# Baby_TX_Mod.net
KiCad netlist of a schematic drawn in EAGLE
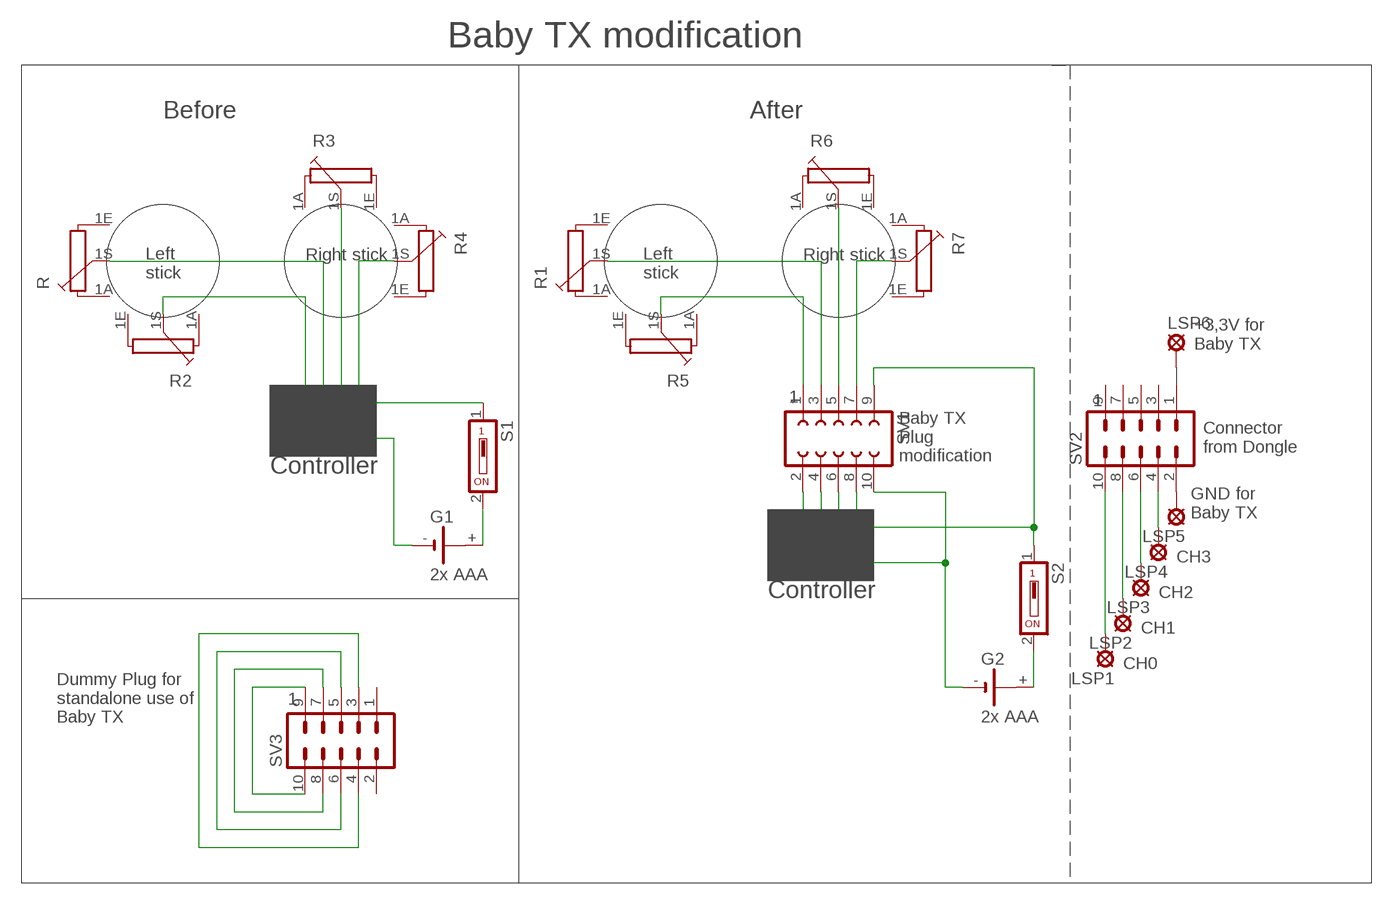
[diagram p0: schematic, sheet 1]

(export (version "E")
  (design (tool "Eeschema 10.0.6"))
  (components
    (comp (ref "G1")
      (value "2x AAA")
      (footprint "eagle-import:CR2032H")
      (libsource (lib "eagle-import") (part "CR2032H"))
    )
    (comp (ref "G2")
      (value "2x AAA")
      (footprint "eagle-import:CR2032H")
      (libsource (lib "eagle-import") (part "CR2032H"))
    )
    (comp (ref "LSP1")
      (value "LSP10")
      (footprint "eagle-import:LSP10")
      (libsource (lib "eagle-import") (part "LSP10"))
    )
    (comp (ref "LSP2")
      (value "LSP10")
      (footprint "eagle-import:LSP10")
      (libsource (lib "eagle-import") (part "LSP10"))
    )
    (comp (ref "LSP3")
      (value "LSP10")
      (footprint "eagle-import:LSP10")
      (libsource (lib "eagle-import") (part "LSP10"))
    )
    (comp (ref "LSP4")
      (value "LSP10")
      (footprint "eagle-import:LSP10")
      (libsource (lib "eagle-import") (part "LSP10"))
    )
    (comp (ref "LSP5")
      (value "LSP10")
      (footprint "eagle-import:LSP10")
      (libsource (lib "eagle-import") (part "LSP10"))
    )
    (comp (ref "LSP6")
      (value "LSP10")
      (footprint "eagle-import:LSP10")
      (libsource (lib "eagle-import") (part "LSP10"))
    )
    (comp (ref "R")
      (value "PC16S")
      (footprint "eagle-import:PC16S")
      (libsource (lib "eagle-import") (part "PC16S"))
    )
    (comp (ref "R1")
      (value "PC16S")
      (footprint "eagle-import:PC16S")
      (libsource (lib "eagle-import") (part "PC16S"))
    )
    (comp (ref "R2")
      (value "PC16S")
      (footprint "eagle-import:PC16S")
      (libsource (lib "eagle-import") (part "PC16S"))
    )
    (comp (ref "R3")
      (value "PC16S")
      (footprint "eagle-import:PC16S")
      (libsource (lib "eagle-import") (part "PC16S"))
    )
    (comp (ref "R4")
      (value "PC16S")
      (footprint "eagle-import:PC16S")
      (libsource (lib "eagle-import") (part "PC16S"))
    )
    (comp (ref "R5")
      (value "PC16S")
      (footprint "eagle-import:PC16S")
      (libsource (lib "eagle-import") (part "PC16S"))
    )
    (comp (ref "R6")
      (value "PC16S")
      (footprint "eagle-import:PC16S")
      (libsource (lib "eagle-import") (part "PC16S"))
    )
    (comp (ref "R7")
      (value "PC16S")
      (footprint "eagle-import:PC16S")
      (libsource (lib "eagle-import") (part "PC16S"))
    )
    (comp (ref "S1")
      (value "SD4-01")
      (footprint "eagle-import:SD4-01")
      (libsource (lib "eagle-import") (part "SD4-01"))
    )
    (comp (ref "S2")
      (value "SD4-01")
      (footprint "eagle-import:SD4-01")
      (libsource (lib "eagle-import") (part "SD4-01"))
    )
    (comp (ref "SV1")
      (value "FE05-2")
      (footprint "eagle-import:FE05-2")
      (libsource (lib "eagle-import") (part "FE05-2"))
    )
    (comp (ref "SV2")
      (value "MA05-2")
      (footprint "eagle-import:MA05-2")
      (libsource (lib "eagle-import") (part "MA05-2"))
    )
    (comp (ref "SV3")
      (value "MA05-2")
      (footprint "eagle-import:MA05-2")
      (libsource (lib "eagle-import") (part "MA05-2"))
    )
  )
  (nets
    (net (code "1") (name "Net-(G1-Pad+)") (class "Default")
      (node (ref "G1") (pin "+") (pinfunction "+_+") (pintype "passive"))
      (node (ref "S1") (pin "2") (pinfunction "2_2") (pintype "passive"))
    )
    (net (code "2") (name "Net-(G2-Pad+)") (class "Default")
      (node (ref "G2") (pin "+") (pinfunction "+_+") (pintype "passive"))
      (node (ref "S2") (pin "2") (pinfunction "2_2") (pintype "passive"))
    )
    (net (code "3") (name "Net-(G2-Pad-)") (class "Default")
      (node (ref "G2") (pin "-") (pinfunction "-_-") (pintype "passive"))
      (node (ref "SV1") (pin "10") (pinfunction "10_10") (pintype "passive"))
    )
    (net (code "4") (name "Net-(LSP1-PadMP)") (class "Default")
      (node (ref "LSP1") (pin "MP") (pinfunction "MP_MP") (pintype "passive"))
      (node (ref "SV2") (pin "10") (pinfunction "10_10") (pintype "passive"))
    )
    (net (code "5") (name "Net-(LSP2-PadMP)") (class "Default")
      (node (ref "LSP2") (pin "MP") (pinfunction "MP_MP") (pintype "passive"))
      (node (ref "SV2") (pin "8") (pinfunction "8_8") (pintype "passive"))
    )
    (net (code "6") (name "Net-(LSP3-PadMP)") (class "Default")
      (node (ref "LSP3") (pin "MP") (pinfunction "MP_MP") (pintype "passive"))
      (node (ref "SV2") (pin "6") (pinfunction "6_6") (pintype "passive"))
    )
    (net (code "7") (name "Net-(LSP4-PadMP)") (class "Default")
      (node (ref "LSP4") (pin "MP") (pinfunction "MP_MP") (pintype "passive"))
      (node (ref "SV2") (pin "4") (pinfunction "4_4") (pintype "passive"))
    )
    (net (code "8") (name "Net-(LSP5-PadMP)") (class "Default")
      (node (ref "LSP5") (pin "MP") (pinfunction "MP_MP") (pintype "passive"))
      (node (ref "SV2") (pin "2") (pinfunction "2_2") (pintype "passive"))
    )
    (net (code "9") (name "Net-(R1-Pad1S)") (class "Default")
      (node (ref "R1") (pin "1S") (pinfunction "1S_1S") (pintype "passive"))
      (node (ref "SV1") (pin "3") (pinfunction "3_3") (pintype "passive"))
    )
    (net (code "10") (name "Net-(R5-Pad1S)") (class "Default")
      (node (ref "R5") (pin "1S") (pinfunction "1S_1S") (pintype "passive"))
      (node (ref "SV1") (pin "1") (pinfunction "1_1") (pintype "passive"))
    )
    (net (code "11") (name "Net-(R6-Pad1S)") (class "Default")
      (node (ref "R6") (pin "1S") (pinfunction "1S_1S") (pintype "passive"))
      (node (ref "SV1") (pin "5") (pinfunction "5_5") (pintype "passive"))
    )
    (net (code "12") (name "Net-(R7-Pad1S)") (class "Default")
      (node (ref "R7") (pin "1S") (pinfunction "1S_1S") (pintype "passive"))
      (node (ref "SV1") (pin "7") (pinfunction "7_7") (pintype "passive"))
    )
    (net (code "13") (name "Net-(S2-Pad1)") (class "Default")
      (node (ref "S2") (pin "1") (pinfunction "1_1") (pintype "passive"))
      (node (ref "SV1") (pin "9") (pinfunction "9_9") (pintype "passive"))
    )
    (net (code "14") (name "Net-(SV3-Pad3)") (class "Default")
      (node (ref "SV3") (pin "3") (pinfunction "3_3") (pintype "passive"))
      (node (ref "SV3") (pin "4") (pinfunction "4_4") (pintype "passive"))
    )
    (net (code "15") (name "Net-(SV3-Pad5)") (class "Default")
      (node (ref "SV3") (pin "5") (pinfunction "5_5") (pintype "passive"))
      (node (ref "SV3") (pin "6") (pinfunction "6_6") (pintype "passive"))
    )
    (net (code "16") (name "Net-(SV3-Pad7)") (class "Default")
      (node (ref "SV3") (pin "7") (pinfunction "7_7") (pintype "passive"))
      (node (ref "SV3") (pin "8") (pinfunction "8_8") (pintype "passive"))
    )
    (net (code "17") (name "Net-(SV3-Pad10)") (class "Default")
      (node (ref "SV3") (pin "10") (pinfunction "10_10") (pintype "passive"))
      (node (ref "SV3") (pin "9") (pinfunction "9_9") (pintype "passive"))
    )
    (net (code "18") (name "unconnected-(G1-+-Pad+@1)") (class "Default")
      (node (ref "G1") (pin "+@1") (pinfunction "+_+@1") (pintype "passive"))
    )
    (net (code "19") (name "unconnected-(G1-Pad-)") (class "Default")
      (node (ref "G1") (pin "-") (pinfunction "-_-") (pintype "passive"))
    )
    (net (code "20") (name "unconnected-(G2-+-Pad+@1)") (class "Default")
      (node (ref "G2") (pin "+@1") (pinfunction "+_+@1") (pintype "passive"))
    )
    (net (code "21") (name "unconnected-(LSP6-PadMP)") (class "Default")
      (node (ref "LSP6") (pin "MP") (pinfunction "MP_MP") (pintype "passive"))
    )
    (net (code "22") (name "unconnected-(R-Pad1A)") (class "Default")
      (node (ref "R") (pin "1A") (pinfunction "1A_1A") (pintype "passive"))
    )
    (net (code "23") (name "unconnected-(R-Pad1E)") (class "Default")
      (node (ref "R") (pin "1E") (pinfunction "1E_1E") (pintype "passive"))
    )
    (net (code "24") (name "unconnected-(R-Pad1S)") (class "Default")
      (node (ref "R") (pin "1S") (pinfunction "1S_1S") (pintype "passive"))
    )
    (net (code "25") (name "unconnected-(R1-Pad1A)") (class "Default")
      (node (ref "R1") (pin "1A") (pinfunction "1A_1A") (pintype "passive"))
    )
    (net (code "26") (name "unconnected-(R1-Pad1E)") (class "Default")
      (node (ref "R1") (pin "1E") (pinfunction "1E_1E") (pintype "passive"))
    )
    (net (code "27") (name "unconnected-(R2-Pad1A)") (class "Default")
      (node (ref "R2") (pin "1A") (pinfunction "1A_1A") (pintype "passive"))
    )
    (net (code "28") (name "unconnected-(R2-Pad1E)") (class "Default")
      (node (ref "R2") (pin "1E") (pinfunction "1E_1E") (pintype "passive"))
    )
    (net (code "29") (name "unconnected-(R2-Pad1S)") (class "Default")
      (node (ref "R2") (pin "1S") (pinfunction "1S_1S") (pintype "passive"))
    )
    (net (code "30") (name "unconnected-(R3-Pad1A)") (class "Default")
      (node (ref "R3") (pin "1A") (pinfunction "1A_1A") (pintype "passive"))
    )
    (net (code "31") (name "unconnected-(R3-Pad1E)") (class "Default")
      (node (ref "R3") (pin "1E") (pinfunction "1E_1E") (pintype "passive"))
    )
    (net (code "32") (name "unconnected-(R3-Pad1S)") (class "Default")
      (node (ref "R3") (pin "1S") (pinfunction "1S_1S") (pintype "passive"))
    )
    (net (code "33") (name "unconnected-(R4-Pad1A)") (class "Default")
      (node (ref "R4") (pin "1A") (pinfunction "1A_1A") (pintype "passive"))
    )
    (net (code "34") (name "unconnected-(R4-Pad1E)") (class "Default")
      (node (ref "R4") (pin "1E") (pinfunction "1E_1E") (pintype "passive"))
    )
    (net (code "35") (name "unconnected-(R4-Pad1S)") (class "Default")
      (node (ref "R4") (pin "1S") (pinfunction "1S_1S") (pintype "passive"))
    )
    (net (code "36") (name "unconnected-(R5-Pad1A)") (class "Default")
      (node (ref "R5") (pin "1A") (pinfunction "1A_1A") (pintype "passive"))
    )
    (net (code "37") (name "unconnected-(R5-Pad1E)") (class "Default")
      (node (ref "R5") (pin "1E") (pinfunction "1E_1E") (pintype "passive"))
    )
    (net (code "38") (name "unconnected-(R6-Pad1A)") (class "Default")
      (node (ref "R6") (pin "1A") (pinfunction "1A_1A") (pintype "passive"))
    )
    (net (code "39") (name "unconnected-(R6-Pad1E)") (class "Default")
      (node (ref "R6") (pin "1E") (pinfunction "1E_1E") (pintype "passive"))
    )
    (net (code "40") (name "unconnected-(R7-Pad1A)") (class "Default")
      (node (ref "R7") (pin "1A") (pinfunction "1A_1A") (pintype "passive"))
    )
    (net (code "41") (name "unconnected-(R7-Pad1E)") (class "Default")
      (node (ref "R7") (pin "1E") (pinfunction "1E_1E") (pintype "passive"))
    )
    (net (code "42") (name "unconnected-(S1-Pad1)") (class "Default")
      (node (ref "S1") (pin "1") (pinfunction "1_1") (pintype "passive"))
    )
    (net (code "43") (name "unconnected-(SV1-Pad2)") (class "Default")
      (node (ref "SV1") (pin "2") (pinfunction "2_2") (pintype "passive"))
    )
    (net (code "44") (name "unconnected-(SV1-Pad4)") (class "Default")
      (node (ref "SV1") (pin "4") (pinfunction "4_4") (pintype "passive"))
    )
    (net (code "45") (name "unconnected-(SV1-Pad6)") (class "Default")
      (node (ref "SV1") (pin "6") (pinfunction "6_6") (pintype "passive"))
    )
    (net (code "46") (name "unconnected-(SV1-Pad8)") (class "Default")
      (node (ref "SV1") (pin "8") (pinfunction "8_8") (pintype "passive"))
    )
    (net (code "47") (name "unconnected-(SV2-Pad1)") (class "Default")
      (node (ref "SV2") (pin "1") (pinfunction "1_1") (pintype "passive"))
    )
    (net (code "48") (name "unconnected-(SV2-Pad3)") (class "Default")
      (node (ref "SV2") (pin "3") (pinfunction "3_3") (pintype "passive"))
    )
    (net (code "49") (name "unconnected-(SV2-Pad5)") (class "Default")
      (node (ref "SV2") (pin "5") (pinfunction "5_5") (pintype "passive"))
    )
    (net (code "50") (name "unconnected-(SV2-Pad7)") (class "Default")
      (node (ref "SV2") (pin "7") (pinfunction "7_7") (pintype "passive"))
    )
    (net (code "51") (name "unconnected-(SV2-Pad9)") (class "Default")
      (node (ref "SV2") (pin "9") (pinfunction "9_9") (pintype "passive"))
    )
    (net (code "52") (name "unconnected-(SV3-Pad1)") (class "Default")
      (node (ref "SV3") (pin "1") (pinfunction "1_1") (pintype "passive"))
    )
    (net (code "53") (name "unconnected-(SV3-Pad2)") (class "Default")
      (node (ref "SV3") (pin "2") (pinfunction "2_2") (pintype "passive"))
    )
  )
)
